# 05_GSM.net
KiCad netlist of a schematic drawn in Altium Designer
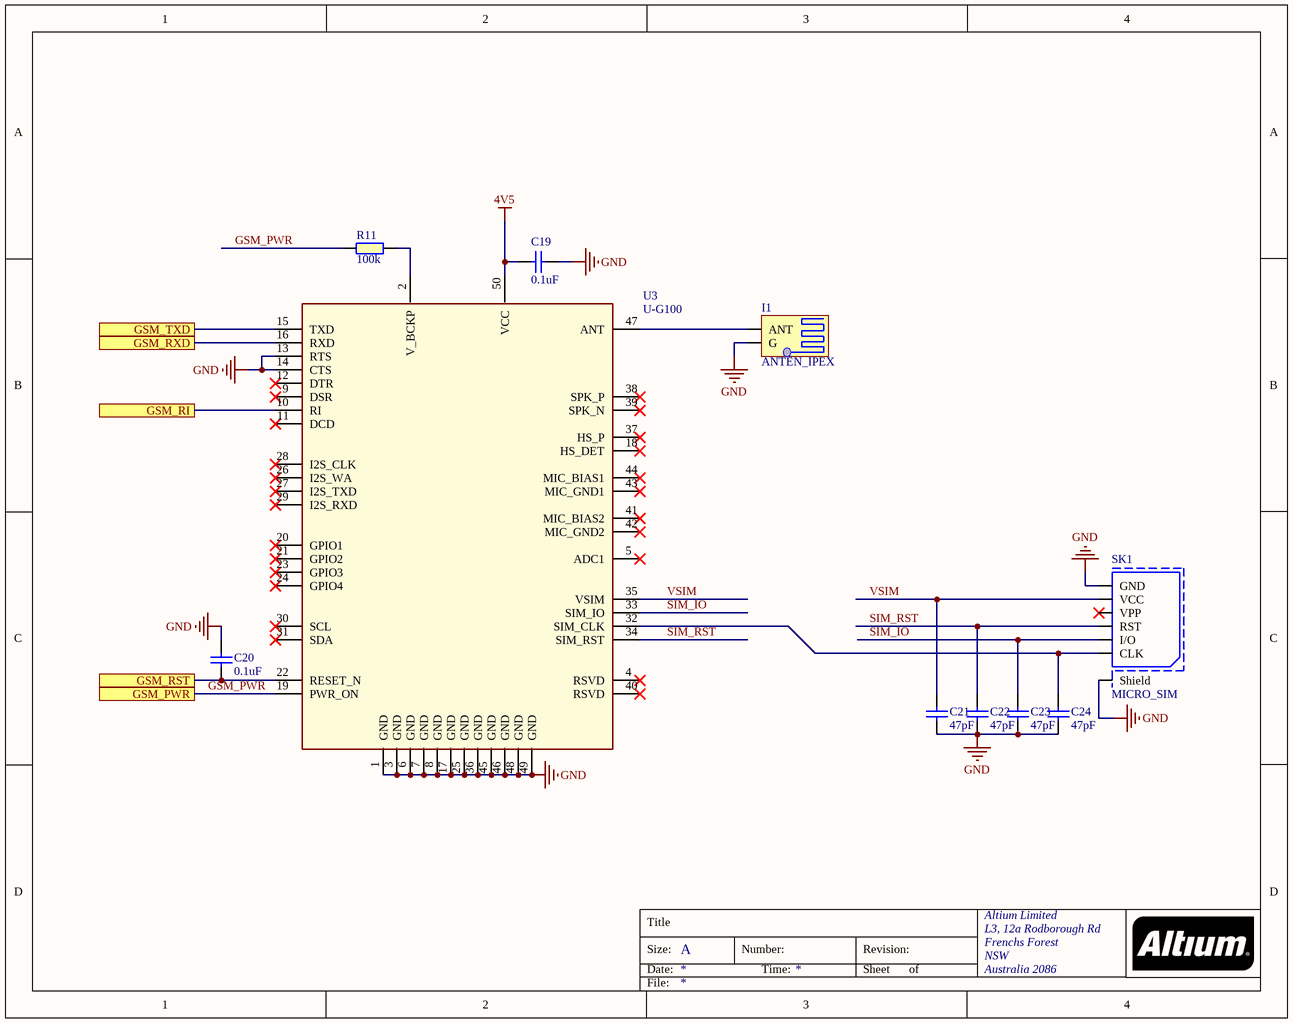
[diagram p0: [05].GSM.SchDoc]

(export (version "E")
  (design (tool "Eeschema 10.0.6"))
  (components
    (comp (ref "C19") (value "0.1uF") (footprint "C_0603") (libsource (lib "DungMV") (part "CAP_0805")))
    (comp (ref "C20") (value "0.1uF") (footprint "C_0603") (libsource (lib "DungMV") (part "CAP_0805")))
    (comp (ref "C21") (value "47pF") (footprint "C_0603") (libsource (lib "DungMV") (part "CAP_0805")))
    (comp (ref "C22") (value "47pF") (footprint "C_0603") (libsource (lib "DungMV") (part "CAP_0805")))
    (comp (ref "C23") (value "47pF") (footprint "C_0603") (libsource (lib "DungMV") (part "CAP_0805")))
    (comp (ref "C24") (value "47pF") (footprint "C_0603") (libsource (lib "DungMV") (part "CAP_0805")))
    (comp (ref "I1")
      (value "ANTEN_IPEX")
      (footprint "ANTEN_IPEX")
      (libsource (lib "DungMV") (part "ANTEN_IPEX"))
    )
    (comp (ref "R11") (value "100k") (footprint "R_0603") (libsource (lib "DungMV") (part "RES_0603")))
    (comp (ref "SK1")
      (value "MICRO_SIM")
      (footprint "MICRO_SIM")
      (libsource (lib "DungMV") (part "MICRO_SIM"))
    )
    (comp (ref "U3") (value "U-G100") (footprint "G100_UBLOX") (libsource (lib "DungMV") (part "U-G100")))
  )
  (nets
    (net (code "1") (name "/GSM_PWR") (class "Default")
      (node (ref "R11") (pin "1") (pinfunction "1_1") (pintype "passive"))
      (node (ref "U3") (pin "19") (pinfunction "PWR_ON_19") (pintype "passive"))
    )
    (net (code "2") (name "/GSM_RI") (class "Default")
      (node (ref "U3") (pin "10") (pinfunction "RI_10") (pintype "passive"))
    )
    (net (code "3") (name "/GSM_RST") (class "Default")
      (node (ref "C20") (pin "2") (pinfunction "2_2") (pintype "passive"))
      (node (ref "U3") (pin "22") (pinfunction "RESET_N_22") (pintype "passive"))
    )
    (net (code "4") (name "/GSM_RXD") (class "Default")
      (node (ref "U3") (pin "16") (pinfunction "RXD_16") (pintype "passive"))
    )
    (net (code "5") (name "/GSM_TXD") (class "Default")
      (node (ref "U3") (pin "15") (pinfunction "TXD_15") (pintype "passive"))
    )
    (net (code "6") (name "/SIM_IO") (class "Default")
      (node (ref "C23") (pin "2") (pinfunction "2_2") (pintype "passive"))
      (node (ref "SK1") (pin "C7") (pinfunction "I/O_C7") (pintype "passive"))
      (node (ref "U3") (pin "33") (pinfunction "SIM_IO_33") (pintype "passive"))
    )
    (net (code "7") (name "/SIM_RST") (class "Default")
      (node (ref "C22") (pin "2") (pinfunction "2_2") (pintype "passive"))
      (node (ref "SK1") (pin "C2") (pinfunction "RST_C2") (pintype "passive"))
      (node (ref "U3") (pin "34") (pinfunction "SIM_RST_34") (pintype "passive"))
    )
    (net (code "8") (name "/VSIM") (class "Default")
      (node (ref "C21") (pin "2") (pinfunction "2_2") (pintype "passive"))
      (node (ref "SK1") (pin "C1") (pinfunction "VCC_C1") (pintype "passive"))
      (node (ref "U3") (pin "35") (pinfunction "VSIM_35") (pintype "passive"))
    )
    (net (code "9") (name "4V5") (class "Default")
      (node (ref "C19") (pin "2") (pinfunction "2_2") (pintype "passive"))
      (node (ref "U3") (pin "50") (pinfunction "VCC_50") (pintype "passive"))
    )
    (net (code "10") (name "GND") (class "Default")
      (node (ref "C19") (pin "1") (pinfunction "1_1") (pintype "passive"))
      (node (ref "C20") (pin "1") (pinfunction "1_1") (pintype "passive"))
      (node (ref "C21") (pin "1") (pinfunction "1_1") (pintype "passive"))
      (node (ref "C22") (pin "1") (pinfunction "1_1") (pintype "passive"))
      (node (ref "C23") (pin "1") (pinfunction "1_1") (pintype "passive"))
      (node (ref "C24") (pin "1") (pinfunction "1_1") (pintype "passive"))
      (node (ref "I1") (pin "2") (pinfunction "G_2") (pintype "passive"))
      (node (ref "SK1") (pin "C5") (pinfunction "GND_C5") (pintype "passive"))
      (node (ref "SK1") (pin "SH1") (pinfunction "Shield_SH1") (pintype "passive"))
      (node (ref "U3") (pin "1") (pinfunction "GND_1") (pintype "passive"))
      (node (ref "U3") (pin "13") (pinfunction "RTS_13") (pintype "passive"))
      (node (ref "U3") (pin "14") (pinfunction "CTS_14") (pintype "passive"))
      (node (ref "U3") (pin "17") (pinfunction "GND_17") (pintype "passive"))
      (node (ref "U3") (pin "25") (pinfunction "GND_25") (pintype "passive"))
      (node (ref "U3") (pin "3") (pinfunction "GND_3") (pintype "passive"))
      (node (ref "U3") (pin "36") (pinfunction "GND_36") (pintype "passive"))
      (node (ref "U3") (pin "45") (pinfunction "GND_45") (pintype "passive"))
      (node (ref "U3") (pin "46") (pinfunction "GND_46") (pintype "passive"))
      (node (ref "U3") (pin "48") (pinfunction "GND_48") (pintype "passive"))
      (node (ref "U3") (pin "49") (pinfunction "GND_49") (pintype "passive"))
      (node (ref "U3") (pin "6") (pinfunction "GND_6") (pintype "passive"))
      (node (ref "U3") (pin "7") (pinfunction "GND_7") (pintype "passive"))
      (node (ref "U3") (pin "8") (pinfunction "GND_8") (pintype "passive"))
    )
    (net (code "11") (name "Net-(I1-ANT)") (class "Default")
      (node (ref "I1") (pin "1") (pinfunction "ANT_1") (pintype "passive"))
      (node (ref "U3") (pin "47") (pinfunction "ANT_47") (pintype "passive"))
    )
    (net (code "12") (name "Net-(SK1-CLK)") (class "Default")
      (node (ref "C24") (pin "2") (pinfunction "2_2") (pintype "passive"))
      (node (ref "SK1") (pin "C3") (pinfunction "CLK_C3") (pintype "passive"))
      (node (ref "U3") (pin "32") (pinfunction "SIM_CLK_32") (pintype "passive"))
    )
    (net (code "13") (name "Net-(U3-V_BCKP)") (class "Default")
      (node (ref "R11") (pin "2") (pinfunction "2_2") (pintype "passive"))
      (node (ref "U3") (pin "2") (pinfunction "V_BCKP_2") (pintype "passive"))
    )
    (net (code "14") (name "unconnected-(SK1-VPP-PadC6)") (class "Default")
      (node (ref "SK1") (pin "C6") (pinfunction "VPP_C6") (pintype "passive+no_connect"))
    )
    (net (code "15") (name "unconnected-(U3-ADC1-Pad5)") (class "Default")
      (node (ref "U3") (pin "5") (pinfunction "ADC1_5") (pintype "passive+no_connect"))
    )
    (net (code "16") (name "unconnected-(U3-DCD-Pad11)") (class "Default")
      (node (ref "U3") (pin "11") (pinfunction "DCD_11") (pintype "passive+no_connect"))
    )
    (net (code "17") (name "unconnected-(U3-DSR-Pad9)") (class "Default")
      (node (ref "U3") (pin "9") (pinfunction "DSR_9") (pintype "passive+no_connect"))
    )
    (net (code "18") (name "unconnected-(U3-DTR-Pad12)") (class "Default")
      (node (ref "U3") (pin "12") (pinfunction "DTR_12") (pintype "passive+no_connect"))
    )
    (net (code "19") (name "unconnected-(U3-GPIO1-Pad20)") (class "Default")
      (node (ref "U3") (pin "20") (pinfunction "GPIO1_20") (pintype "passive+no_connect"))
    )
    (net (code "20") (name "unconnected-(U3-GPIO2-Pad21)") (class "Default")
      (node (ref "U3") (pin "21") (pinfunction "GPIO2_21") (pintype "passive+no_connect"))
    )
    (net (code "21") (name "unconnected-(U3-GPIO3-Pad23)") (class "Default")
      (node (ref "U3") (pin "23") (pinfunction "GPIO3_23") (pintype "passive+no_connect"))
    )
    (net (code "22") (name "unconnected-(U3-GPIO4-Pad24)") (class "Default")
      (node (ref "U3") (pin "24") (pinfunction "GPIO4_24") (pintype "passive+no_connect"))
    )
    (net (code "23") (name "unconnected-(U3-HS_DET-Pad18)") (class "Default")
      (node (ref "U3") (pin "18") (pinfunction "HS_DET_18") (pintype "passive+no_connect"))
    )
    (net (code "24") (name "unconnected-(U3-HS_P-Pad37)") (class "Default")
      (node (ref "U3") (pin "37") (pinfunction "HS_P_37") (pintype "passive+no_connect"))
    )
    (net (code "25") (name "unconnected-(U3-I2S_CLK-Pad28)") (class "Default")
      (node (ref "U3") (pin "28") (pinfunction "I2S_CLK_28") (pintype "passive+no_connect"))
    )
    (net (code "26") (name "unconnected-(U3-I2S_RXD-Pad29)") (class "Default")
      (node (ref "U3") (pin "29") (pinfunction "I2S_RXD_29") (pintype "passive+no_connect"))
    )
    (net (code "27") (name "unconnected-(U3-I2S_TXD-Pad27)") (class "Default")
      (node (ref "U3") (pin "27") (pinfunction "I2S_TXD_27") (pintype "passive+no_connect"))
    )
    (net (code "28") (name "unconnected-(U3-I2S_WA-Pad26)") (class "Default")
      (node (ref "U3") (pin "26") (pinfunction "I2S_WA_26") (pintype "passive+no_connect"))
    )
    (net (code "29") (name "unconnected-(U3-MIC_BIAS1-Pad44)") (class "Default")
      (node (ref "U3") (pin "44") (pinfunction "MIC_BIAS1_44") (pintype "passive+no_connect"))
    )
    (net (code "30") (name "unconnected-(U3-MIC_BIAS2-Pad41)") (class "Default")
      (node (ref "U3") (pin "41") (pinfunction "MIC_BIAS2_41") (pintype "passive+no_connect"))
    )
    (net (code "31") (name "unconnected-(U3-MIC_GND1-Pad43)") (class "Default")
      (node (ref "U3") (pin "43") (pinfunction "MIC_GND1_43") (pintype "passive+no_connect"))
    )
    (net (code "32") (name "unconnected-(U3-MIC_GND2-Pad42)") (class "Default")
      (node (ref "U3") (pin "42") (pinfunction "MIC_GND2_42") (pintype "passive+no_connect"))
    )
    (net (code "33") (name "unconnected-(U3-RSVD-Pad4)") (class "Default")
      (node (ref "U3") (pin "4") (pinfunction "RSVD_4") (pintype "passive+no_connect"))
    )
    (net (code "34") (name "unconnected-(U3-RSVD-Pad40)") (class "Default")
      (node (ref "U3") (pin "40") (pinfunction "RSVD_40") (pintype "passive+no_connect"))
    )
    (net (code "35") (name "unconnected-(U3-SCL-Pad30)") (class "Default")
      (node (ref "U3") (pin "30") (pinfunction "SCL_30") (pintype "passive+no_connect"))
    )
    (net (code "36") (name "unconnected-(U3-SDA-Pad31)") (class "Default")
      (node (ref "U3") (pin "31") (pinfunction "SDA_31") (pintype "passive+no_connect"))
    )
    (net (code "37") (name "unconnected-(U3-SPK_N-Pad39)") (class "Default")
      (node (ref "U3") (pin "39") (pinfunction "SPK_N_39") (pintype "passive+no_connect"))
    )
    (net (code "38") (name "unconnected-(U3-SPK_P-Pad38)") (class "Default")
      (node (ref "U3") (pin "38") (pinfunction "SPK_P_38") (pintype "passive+no_connect"))
    )
  )
)
